# CLK_INPUT.net
KiCad netlist of a schematic drawn in Altium Designer
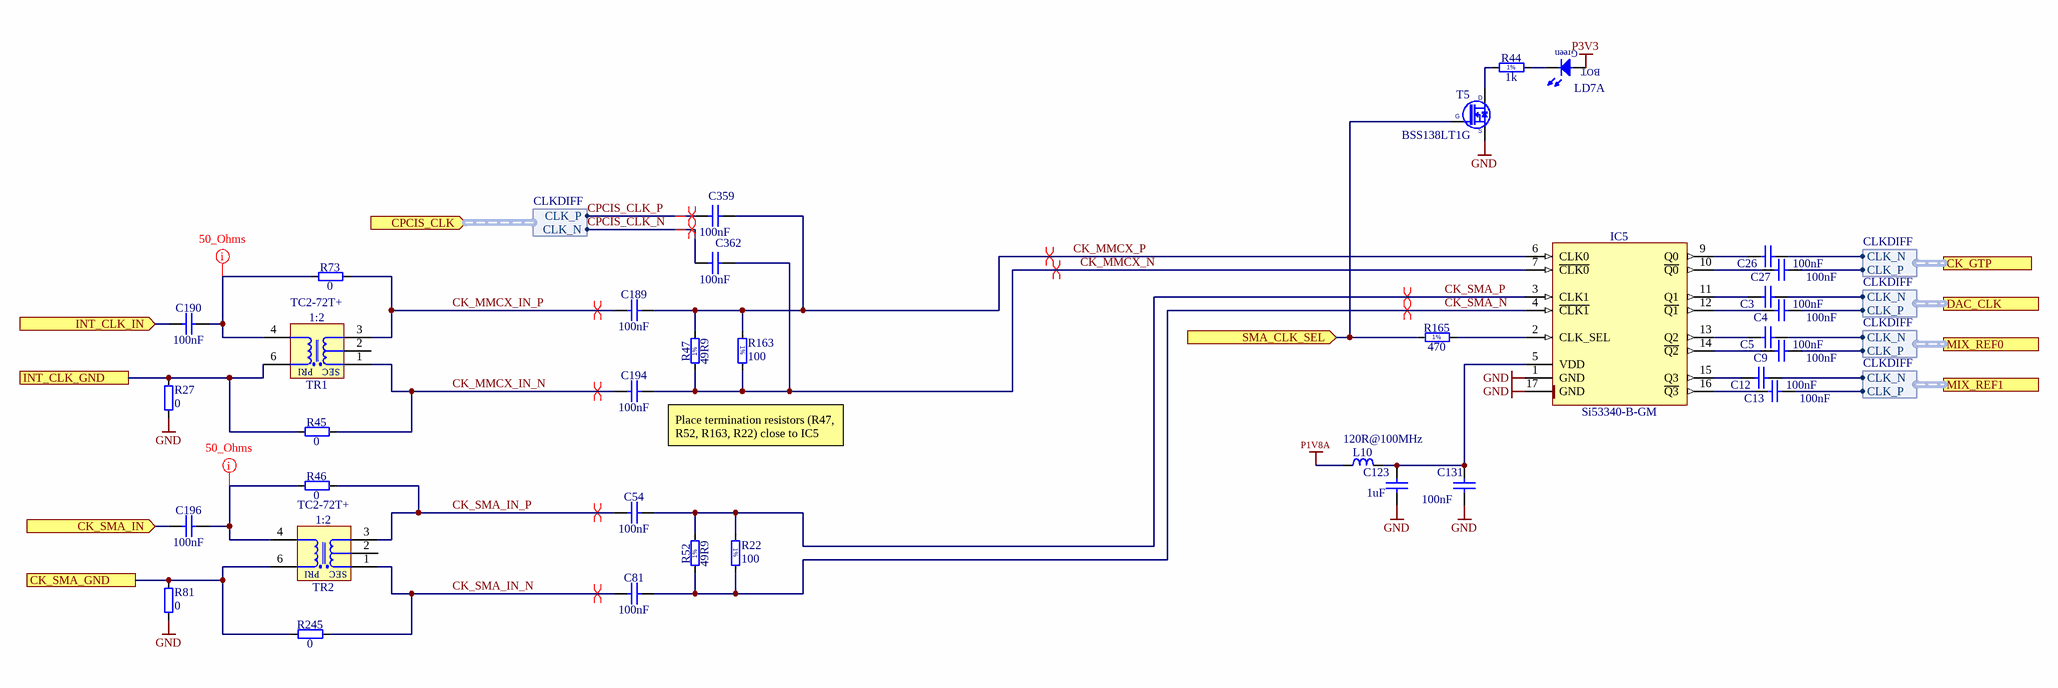
[diagram p0: CLK_INPUT.SchDoc]

(export (version "E")
  (design (tool "Eeschema 10.0.6"))
  (components
    (comp (ref "C3")
      (value "100nF")
      (footprint "CAPC1005X55N")
      (description "Non-polarised capacitor")
      (fields
        (field (name "PART NUMBER") "CC0402_100NF_16V_10%_X5R")
        (field (name "VOLTAGE") "16V")
        (field (name "AUTHOR") "CERN DEM JLC")
      )
      (libsource (lib "Capacitors") (part "Capacitor - non polarized"))
    )
    (comp (ref "C4")
      (value "100nF")
      (footprint "CAPC1005X55N")
      (description "Non-polarised capacitor")
      (fields
        (field (name "PART NUMBER") "CC0402_100NF_16V_10%_X5R")
        (field (name "VOLTAGE") "16V")
        (field (name "AUTHOR") "CERN DEM JLC")
      )
      (libsource (lib "Capacitors") (part "Capacitor - non polarized"))
    )
    (comp (ref "C5")
      (value "100nF")
      (footprint "CAPC1005X55N")
      (description "Non-polarised capacitor")
      (fields
        (field (name "PART NUMBER") "CC0402_100NF_16V_10%_X5R")
        (field (name "VOLTAGE") "16V")
        (field (name "AUTHOR") "CERN DEM JLC")
      )
      (libsource (lib "Capacitors") (part "Capacitor - non polarized"))
    )
    (comp (ref "C9")
      (value "100nF")
      (footprint "CAPC1005X55N")
      (description "Non-polarised capacitor")
      (fields
        (field (name "PART NUMBER") "CC0402_100NF_16V_10%_X5R")
        (field (name "VOLTAGE") "16V")
        (field (name "AUTHOR") "CERN DEM JLC")
      )
      (libsource (lib "Capacitors") (part "Capacitor - non polarized"))
    )
    (comp (ref "C12")
      (value "100nF")
      (footprint "CAPC1005X55N")
      (description "Non-polarised capacitor")
      (fields
        (field (name "PART NUMBER") "CC0402_100NF_16V_10%_X5R")
        (field (name "VOLTAGE") "16V")
        (field (name "AUTHOR") "CERN DEM JLC")
      )
      (libsource (lib "Capacitors") (part "Capacitor - non polarized"))
    )
    (comp (ref "C13")
      (value "100nF")
      (footprint "CAPC1005X55N")
      (description "Non-polarised capacitor")
      (fields
        (field (name "PART NUMBER") "CC0402_100NF_16V_10%_X5R")
        (field (name "VOLTAGE") "16V")
        (field (name "AUTHOR") "CERN DEM JLC")
      )
      (libsource (lib "Capacitors") (part "Capacitor - non polarized"))
    )
    (comp (ref "C26")
      (value "100nF")
      (footprint "CAPC1005X55N")
      (description "Non-polarised capacitor")
      (fields
        (field (name "PART NUMBER") "CC0402_100NF_16V_10%_X5R")
        (field (name "VOLTAGE") "16V")
        (field (name "AUTHOR") "CERN DEM JLC")
      )
      (libsource (lib "Capacitors") (part "Capacitor - non polarized"))
    )
    (comp (ref "C27")
      (value "100nF")
      (footprint "CAPC1005X55N")
      (description "Non-polarised capacitor")
      (fields
        (field (name "PART NUMBER") "CC0402_100NF_16V_10%_X5R")
        (field (name "VOLTAGE") "16V")
        (field (name "AUTHOR") "CERN DEM JLC")
      )
      (libsource (lib "Capacitors") (part "Capacitor - non polarized"))
    )
    (comp (ref "C54")
      (value "100nF")
      (footprint "CAPC1005X55N")
      (description "Non-polarised capacitor")
      (fields
        (field (name "PART NUMBER") "CC0402_100NF_16V_10%_X5R")
        (field (name "VOLTAGE") "16V")
        (field (name "AUTHOR") "CERN DEM JLC")
      )
      (libsource (lib "Capacitors") (part "Capacitor - non polarized"))
    )
    (comp (ref "C81")
      (value "100nF")
      (footprint "CAPC1005X55N")
      (description "Non-polarised capacitor")
      (fields
        (field (name "PART NUMBER") "CC0402_100NF_16V_10%_X5R")
        (field (name "VOLTAGE") "16V")
        (field (name "AUTHOR") "CERN DEM JLC")
      )
      (libsource (lib "Capacitors") (part "Capacitor - non polarized"))
    )
    (comp (ref "C123")
      (value "1uF")
      (footprint "CAPC1005X55N")
      (description "Non-polarised capacitor")
      (fields
        (field (name "PART NUMBER") "CC0402_1UF_16V_10%_X5R")
        (field (name "VOLTAGE") "16V")
        (field (name "AUTHOR") "CERN DEM JLC")
      )
      (libsource (lib "Capacitors") (part "Capacitor - non polarized"))
    )
    (comp (ref "C131")
      (value "100nF")
      (footprint "CAPC1005X55N")
      (description "Non-polarised capacitor")
      (fields
        (field (name "PART NUMBER") "CC0402_100NF_16V_10%_X5R")
        (field (name "VOLTAGE") "16V")
        (field (name "AUTHOR") "CERN DEM JLC")
      )
      (libsource (lib "Capacitors") (part "Capacitor - non polarized"))
    )
    (comp (ref "C189")
      (value "100nF")
      (footprint "CAPC1005X55N")
      (description "Non-polarised capacitor")
      (fields
        (field (name "PART NUMBER") "CC0402_100NF_16V_10%_X5R")
        (field (name "VOLTAGE") "16V")
        (field (name "AUTHOR") "CERN DEM JLC")
      )
      (libsource (lib "Capacitors") (part "Capacitor - non polarized"))
    )
    (comp (ref "C190")
      (value "100nF")
      (footprint "CAPC1005X55N")
      (description "Non-polarised capacitor")
      (fields
        (field (name "PART NUMBER") "CC0402_100NF_16V_10%_X5R")
        (field (name "VOLTAGE") "16V")
        (field (name "AUTHOR") "CERN DEM JLC")
      )
      (libsource (lib "Capacitors") (part "Capacitor - non polarized"))
    )
    (comp (ref "C194")
      (value "100nF")
      (footprint "CAPC1005X55N")
      (description "Non-polarised capacitor")
      (fields
        (field (name "PART NUMBER") "CC0402_100NF_16V_10%_X5R")
        (field (name "VOLTAGE") "16V")
        (field (name "AUTHOR") "CERN DEM JLC")
      )
      (libsource (lib "Capacitors") (part "Capacitor - non polarized"))
    )
    (comp (ref "C196")
      (value "100nF")
      (footprint "CAPC1005X55N")
      (description "Non-polarised capacitor")
      (fields
        (field (name "PART NUMBER") "CC0402_100NF_16V_10%_X5R")
        (field (name "VOLTAGE") "16V")
        (field (name "AUTHOR") "CERN DEM JLC")
      )
      (libsource (lib "Capacitors") (part "Capacitor - non polarized"))
    )
    (comp (ref "C359")
      (value "100nF")
      (footprint "CAPC1005X55N")
      (description "Non-polarised capacitor")
      (fields
        (field (name "PART NUMBER") "CC0402_100NF_16V_10%_X5R")
        (field (name "VOLTAGE") "16V")
        (field (name "AUTHOR") "CERN DEM JLC")
      )
      (libsource (lib "Capacitors") (part "Capacitor - non polarized"))
    )
    (comp (ref "C362")
      (value "100nF")
      (footprint "CAPC1005X55N")
      (description "Non-polarised capacitor")
      (fields
        (field (name "PART NUMBER") "CC0402_100NF_16V_10%_X5R")
        (field (name "VOLTAGE") "16V")
        (field (name "AUTHOR") "CERN DEM JLC")
      )
      (libsource (lib "Capacitors") (part "Capacitor - non polarized"))
    )
    (comp (ref "IC5")
      (value "Si53340-B-GM")
      (footprint "QFN50P300X300X90-17N-S175")
      (description "Low-Jitter LVDS Fanout Clock Buffers, 10-Output,  Any-Input, Any-Frequency up to 1250MHz")
      (fields (field (name "MANUFACTURER") "SILICON LABS") (field (name "AUTHOR") "CERN DEM MR"))
      (libsource (lib "ICs And Semiconductors") (part "Si53340"))
    )
    (comp (ref "L10")
      (value "120R@100MHz")
      (footprint "INDC1608X95N")
      (description "Inductor")
      (fields
        (field (name "PART NUMBER") "IND0603_MURATA_BLM18PG121SN1D")
        (field (name "POWER") "2A")
        (field (name "AUTHOR") "CERN DEM BC")
      )
      (libsource (lib "Inductors & Transformers") (part "Inductor"))
    )
    (comp (ref "LD7")
      (value "Red/Green")
      (footprint "LED_DIALIGHT_571-0112F")
      (description "2x LED  Botom Green, Top Red")
      (fields
        (field (name "PART NUMBER") "LED_DIALIGHT_571-0112F")
        (field (name "MANUFACTURER") "DIALIGHT")
        (field (name "AUTHOR") "CERN DEM JLC")
      )
      (libsource (lib "ICs And Semiconductors") (part "LED x2 G-1C2A-BOT_R-3C4A-TOP"))
    )
    (comp (ref "R22")
      (value "100")
      (footprint "RESC1005X40N")
      (description "Resistor - 1%")
      (fields
        (field (name "PART NUMBER") "R0402_100R_1%_0.0625W_100PPM")
        (field (name "POWER") "0.0625W")
        (field (name "AUTHOR") "CERN DEM JLC")
      )
      (libsource (lib "Resistors") (part "Resistor - 1%"))
    )
    (comp (ref "R27")
      (value "0")
      (footprint "RESC1005X40N")
      (description "Resistor")
      (fields
        (field (name "PART NUMBER") "R0402_0R_JUMPER")
        (field (name "MANUFACTURER") "GENERIC")
        (field (name "AUTHOR") "CERN DEM JLC")
      )
      (libsource (lib "Resistors") (part "Resistor"))
    )
    (comp (ref "R44")
      (value "1k")
      (footprint "RESC1005X40N")
      (description "Resistor - 1%")
      (fields
        (field (name "PART NUMBER") "R0402_1K_1%_0.0625W_100PPM")
        (field (name "POWER") "0.0625W")
        (field (name "AUTHOR") "CERN DEM JLC")
      )
      (libsource (lib "Resistors") (part "Resistor - 1%"))
    )
    (comp (ref "R45")
      (value "0")
      (footprint "RESC1005X40N")
      (description "Resistor")
      (fields
        (field (name "PART NUMBER") "R0402_0R_JUMPER")
        (field (name "MANUFACTURER") "GENERIC")
        (field (name "AUTHOR") "CERN DEM JLC")
      )
      (libsource (lib "Resistors") (part "Resistor"))
    )
    (comp (ref "R46")
      (value "0")
      (footprint "RESC1005X40N")
      (description "Resistor")
      (fields
        (field (name "PART NUMBER") "R0402_0R_JUMPER")
        (field (name "MANUFACTURER") "GENERIC")
        (field (name "AUTHOR") "CERN DEM JLC")
      )
      (libsource (lib "Resistors") (part "Resistor"))
    )
    (comp (ref "R47")
      (value "49R9")
      (footprint "RESC1005X40N")
      (description "Resistor - 1%")
      (fields
        (field (name "PART NUMBER") "R0402_49R9_1%_0.0625W_100PPM")
        (field (name "POWER") "0.0625W")
        (field (name "AUTHOR") "CERN DEM JLC")
      )
      (libsource (lib "Resistors") (part "Resistor - 1%"))
    )
    (comp (ref "R52")
      (value "49R9")
      (footprint "RESC1005X40N")
      (description "Resistor - 1%")
      (fields
        (field (name "PART NUMBER") "R0402_49R9_1%_0.0625W_100PPM")
        (field (name "POWER") "0.0625W")
        (field (name "AUTHOR") "CERN DEM JLC")
      )
      (libsource (lib "Resistors") (part "Resistor - 1%"))
    )
    (comp (ref "R73")
      (value "0")
      (footprint "RESC1005X40N")
      (description "Resistor")
      (fields
        (field (name "PART NUMBER") "R0402_0R_JUMPER")
        (field (name "MANUFACTURER") "GENERIC")
        (field (name "AUTHOR") "CERN DEM JLC")
      )
      (libsource (lib "Resistors") (part "Resistor"))
    )
    (comp (ref "R81")
      (value "0")
      (footprint "RESC1005X40N")
      (description "Resistor")
      (fields
        (field (name "PART NUMBER") "R0402_0R_JUMPER")
        (field (name "MANUFACTURER") "GENERIC")
        (field (name "AUTHOR") "CERN DEM JLC")
      )
      (libsource (lib "Resistors") (part "Resistor"))
    )
    (comp (ref "R163")
      (value "100")
      (footprint "RESC1005X40N")
      (description "Resistor - 1%")
      (fields
        (field (name "PART NUMBER") "R0402_100R_1%_0.0625W_100PPM")
        (field (name "POWER") "0.0625W")
        (field (name "AUTHOR") "CERN DEM JLC")
      )
      (libsource (lib "Resistors") (part "Resistor - 1%"))
    )
    (comp (ref "R165")
      (value "470")
      (footprint "RESC1005X40N")
      (description "Resistor - 1%")
      (fields
        (field (name "PART NUMBER") "R0402_470R_1%_0.0625W_100PPM")
        (field (name "POWER") "0.0625W")
        (field (name "AUTHOR") "CERN DEM JLC")
      )
      (libsource (lib "Resistors") (part "Resistor - 1%"))
    )
    (comp (ref "R245")
      (value "0")
      (footprint "RESC1005X40N")
      (description "Resistor")
      (fields
        (field (name "PART NUMBER") "R0402_0R_JUMPER")
        (field (name "MANUFACTURER") "GENERIC")
        (field (name "AUTHOR") "CERN DEM JLC")
      )
      (libsource (lib "Resistors") (part "Resistor"))
    )
    (comp (ref "T5")
      (value "BSS138LT1G")
      (footprint "SOT95P240X110-3N")
      (description "N-CHANNEL MOSFET WITH DIODE")
      (fields (field (name "MANUFACTURER") "ON SEMICONDUCTOR") (field (name "AUTHOR") "CERN DEM JLC"))
      (libsource (lib "ICs And Semiconductors") (part "N-MOSFET-D 1G 2S 3D"))
    )
    (comp (ref "TR1")
      (value "1:2")
      (footprint "XFMR_MINI-CIRCUITS_AT1521")
      (description "50 Ohms 10 to 700 MHzz RF Transformer")
      (fields
        (field (name "MANUFACTURER") "MINI-CIRCUITS")
        (field (name "MANUFACTURER PART NUMBER") "TC2-72T+")
        (field (name "PART NUMBER") "XFMR_MINI-CIRCUITS_TC2-72T+")
        (field (name "AUTHOR") "GK")
      )
      (libsource (lib "Inductors_Transformers") (part "XFMR_MINI-CIRCUITS_TC2-72T+"))
    )
    (comp (ref "TR2")
      (value "1:2")
      (footprint "XFMR_MINI-CIRCUITS_AT1521")
      (description "50 Ohms 10 to 700 MHzz RF Transformer")
      (fields
        (field (name "MANUFACTURER") "MINI-CIRCUITS")
        (field (name "MANUFACTURER PART NUMBER") "TC2-72T+")
        (field (name "PART NUMBER") "XFMR_MINI-CIRCUITS_TC2-72T+")
        (field (name "AUTHOR") "GK")
      )
      (libsource (lib "Inductors_Transformers") (part "XFMR_MINI-CIRCUITS_TC2-72T+"))
    )
  )
  (nets
    (net (code "2") (name "/CK_MMCX_IN_N") (class "Default")
      (node (ref "C194") (pin "1") (pinfunction "1_1") (pintype "passive"))
      (node (ref "R45") (pin "2") (pinfunction "2_2") (pintype "passive"))
      (node (ref "TR1") (pin "1") (pinfunction "SDOT_1") (pintype "passive"))
    )
    (net (code "3") (name "/CK_MMCX_IN_P") (class "Default")
      (node (ref "C189") (pin "1") (pinfunction "1_1") (pintype "passive"))
      (node (ref "R73") (pin "2") (pinfunction "2_2") (pintype "passive"))
      (node (ref "TR1") (pin "3") (pinfunction "S_3") (pintype "passive"))
    )
    (net (code "4") (name "/CK_MMCX_N") (class "Default")
      (node (ref "C194") (pin "2") (pinfunction "2_2") (pintype "passive"))
      (node (ref "C362") (pin "2") (pinfunction "2_2") (pintype "passive"))
      (node (ref "IC5") (pin "7") (pinfunction "~{CLK0}_7") (pintype "input"))
      (node (ref "R163") (pin "2") (pinfunction "2_2") (pintype "passive"))
      (node (ref "R47") (pin "1") (pinfunction "1_1") (pintype "passive"))
    )
    (net (code "5") (name "/CK_MMCX_P") (class "Default")
      (node (ref "C189") (pin "2") (pinfunction "2_2") (pintype "passive"))
      (node (ref "C359") (pin "2") (pinfunction "2_2") (pintype "passive"))
      (node (ref "IC5") (pin "6") (pinfunction "CLK0_6") (pintype "input"))
      (node (ref "R163") (pin "1") (pinfunction "1_1") (pintype "passive"))
      (node (ref "R47") (pin "2") (pinfunction "2_2") (pintype "passive"))
    )
    (net (code "6") (name "/CK_SMA_GND") (class "Default")
      (node (ref "R245") (pin "1") (pinfunction "1_1") (pintype "passive"))
      (node (ref "R81") (pin "2") (pinfunction "2_2") (pintype "passive"))
      (node (ref "TR2") (pin "6") (pinfunction "PDOT_6") (pintype "passive"))
    )
    (net (code "7") (name "/CK_SMA_IN") (class "Default")
      (node (ref "C196") (pin "1") (pinfunction "1_1") (pintype "passive"))
    )
    (net (code "8") (name "/CK_SMA_IN_N") (class "Default")
      (node (ref "C81") (pin "1") (pinfunction "1_1") (pintype "passive"))
      (node (ref "R245") (pin "2") (pinfunction "2_2") (pintype "passive"))
      (node (ref "TR2") (pin "1") (pinfunction "SDOT_1") (pintype "passive"))
    )
    (net (code "9") (name "/CK_SMA_IN_P") (class "Default")
      (node (ref "C54") (pin "1") (pinfunction "1_1") (pintype "passive"))
      (node (ref "R46") (pin "2") (pinfunction "2_2") (pintype "passive"))
      (node (ref "TR2") (pin "3") (pinfunction "S_3") (pintype "passive"))
    )
    (net (code "10") (name "/CK_SMA_N") (class "Default")
      (node (ref "C81") (pin "2") (pinfunction "2_2") (pintype "passive"))
      (node (ref "IC5") (pin "4") (pinfunction "~{CLK1}_4") (pintype "input"))
      (node (ref "R22") (pin "2") (pinfunction "2_2") (pintype "passive"))
      (node (ref "R52") (pin "1") (pinfunction "1_1") (pintype "passive"))
    )
    (net (code "11") (name "/CK_SMA_P") (class "Default")
      (node (ref "C54") (pin "2") (pinfunction "2_2") (pintype "passive"))
      (node (ref "IC5") (pin "3") (pinfunction "CLK1_3") (pintype "input"))
      (node (ref "R22") (pin "1") (pinfunction "1_1") (pintype "passive"))
      (node (ref "R52") (pin "2") (pinfunction "2_2") (pintype "passive"))
    )
    (net (code "12") (name "/CPCIS_CLK_N") (class "Default")
      (node (ref "C362") (pin "1") (pinfunction "1_1") (pintype "passive"))
    )
    (net (code "13") (name "/CPCIS_CLK_P") (class "Default")
      (node (ref "C359") (pin "1") (pinfunction "1_1") (pintype "passive"))
    )
    (net (code "14") (name "/INT_CLK_GND") (class "Default")
      (node (ref "R27") (pin "2") (pinfunction "2_2") (pintype "passive"))
      (node (ref "R45") (pin "1") (pinfunction "1_1") (pintype "passive"))
      (node (ref "TR1") (pin "6") (pinfunction "PDOT_6") (pintype "passive"))
    )
    (net (code "15") (name "/INT_CLK_IN") (class "Default")
      (node (ref "C190") (pin "1") (pinfunction "1_1") (pintype "passive"))
    )
    (net (code "16") (name "/SMA_CLK_SEL") (class "Default")
      (node (ref "R165") (pin "1") (pinfunction "1_1") (pintype "passive"))
      (node (ref "T5") (pin "1") (pinfunction "G_1") (pintype "passive"))
    )
    (net (code "18") (name "GND") (class "Default")
      (node (ref "C123") (pin "1") (pinfunction "1_1") (pintype "passive"))
      (node (ref "C131") (pin "1") (pinfunction "1_1") (pintype "passive"))
      (node (ref "IC5") (pin "1") (pinfunction "GND_1") (pintype "power_in"))
      (node (ref "IC5") (pin "17") (pinfunction "GND_17") (pintype "power_in"))
      (node (ref "R27") (pin "1") (pinfunction "1_1") (pintype "passive"))
      (node (ref "R81") (pin "1") (pinfunction "1_1") (pintype "passive"))
      (node (ref "T5") (pin "2") (pinfunction "S_2") (pintype "passive"))
    )
    (net (code "19") (name "Net-(IC5-CLK_SEL)") (class "Default")
      (node (ref "IC5") (pin "2") (pinfunction "CLK_SEL_2") (pintype "input"))
      (node (ref "R165") (pin "2") (pinfunction "2_2") (pintype "passive"))
    )
    (net (code "20") (name "Net-(IC5-Q0)") (class "Default")
      (node (ref "C26") (pin "1") (pinfunction "1_1") (pintype "passive"))
      (node (ref "IC5") (pin "9") (pinfunction "Q0_9") (pintype "output"))
    )
    (net (code "21") (name "Net-(IC5-Q1)") (class "Default")
      (node (ref "C3") (pin "1") (pinfunction "1_1") (pintype "passive"))
      (node (ref "IC5") (pin "11") (pinfunction "Q1_11") (pintype "output"))
    )
    (net (code "22") (name "Net-(IC5-Q2)") (class "Default")
      (node (ref "C5") (pin "1") (pinfunction "1_1") (pintype "passive"))
      (node (ref "IC5") (pin "13") (pinfunction "Q2_13") (pintype "output"))
    )
    (net (code "23") (name "Net-(IC5-Q3)") (class "Default")
      (node (ref "C12") (pin "1") (pinfunction "1_1") (pintype "passive"))
      (node (ref "IC5") (pin "15") (pinfunction "Q3_15") (pintype "output"))
    )
    (net (code "24") (name "Net-(IC5-VDD)") (class "Default")
      (node (ref "C123") (pin "2") (pinfunction "2_2") (pintype "passive"))
      (node (ref "C131") (pin "2") (pinfunction "2_2") (pintype "passive"))
      (node (ref "IC5") (pin "5") (pinfunction "VDD_5") (pintype "power_in"))
      (node (ref "L10") (pin "1") (pinfunction "1_1") (pintype "passive"))
    )
    (net (code "25") (name "Net-(IC5-~{Q0})") (class "Default")
      (node (ref "C27") (pin "1") (pinfunction "1_1") (pintype "passive"))
      (node (ref "IC5") (pin "10") (pinfunction "~{Q0}_10") (pintype "output"))
    )
    (net (code "26") (name "Net-(IC5-~{Q1})") (class "Default")
      (node (ref "C4") (pin "1") (pinfunction "1_1") (pintype "passive"))
      (node (ref "IC5") (pin "12") (pinfunction "~{Q1}_12") (pintype "output"))
    )
    (net (code "27") (name "Net-(IC5-~{Q2})") (class "Default")
      (node (ref "C9") (pin "1") (pinfunction "1_1") (pintype "passive"))
      (node (ref "IC5") (pin "14") (pinfunction "~{Q2}_14") (pintype "output"))
    )
    (net (code "28") (name "Net-(IC5-~{Q3})") (class "Default")
      (node (ref "C13") (pin "1") (pinfunction "1_1") (pintype "passive"))
      (node (ref "IC5") (pin "16") (pinfunction "~{Q3}_16") (pintype "output"))
    )
    (net (code "29") (name "Net-(LD7A-C)") (class "Default")
      (node (ref "LD7") (pin "1") (pinfunction "C_1") (pintype "passive"))
      (node (ref "R44") (pin "2") (pinfunction "2_2") (pintype "passive"))
    )
    (net (code "30") (name "Net-(T5-D)") (class "Default")
      (node (ref "R44") (pin "1") (pinfunction "1_1") (pintype "passive"))
      (node (ref "T5") (pin "3") (pinfunction "D_3") (pintype "passive"))
    )
    (net (code "31") (name "Net-(TR1-P)") (class "Default")
      (node (ref "C190") (pin "2") (pinfunction "2_2") (pintype "passive"))
      (node (ref "R73") (pin "1") (pinfunction "1_1") (pintype "passive"))
      (node (ref "TR1") (pin "4") (pinfunction "P_4") (pintype "passive"))
    )
    (net (code "32") (name "Net-(TR2-P)") (class "Default")
      (node (ref "C196") (pin "2") (pinfunction "2_2") (pintype "passive"))
      (node (ref "R46") (pin "1") (pinfunction "1_1") (pintype "passive"))
      (node (ref "TR2") (pin "4") (pinfunction "P_4") (pintype "passive"))
    )
    (net (code "33") (name "P1V8A") (class "Default")
      (node (ref "L10") (pin "2") (pinfunction "2_2") (pintype "passive"))
    )
    (net (code "34") (name "P3V3") (class "Default")
      (node (ref "LD7") (pin "2") (pinfunction "A_2") (pintype "passive"))
    )
    (net (code "35") (name "unconnected-(C3-Pad2)") (class "Default")
      (node (ref "C3") (pin "2") (pinfunction "2_2") (pintype "passive"))
    )
    (net (code "36") (name "unconnected-(C4-Pad2)") (class "Default")
      (node (ref "C4") (pin "2") (pinfunction "2_2") (pintype "passive"))
    )
    (net (code "37") (name "unconnected-(C5-Pad2)") (class "Default")
      (node (ref "C5") (pin "2") (pinfunction "2_2") (pintype "passive"))
    )
    (net (code "38") (name "unconnected-(C9-Pad2)") (class "Default")
      (node (ref "C9") (pin "2") (pinfunction "2_2") (pintype "passive"))
    )
    (net (code "39") (name "unconnected-(C12-Pad2)") (class "Default")
      (node (ref "C12") (pin "2") (pinfunction "2_2") (pintype "passive"))
    )
    (net (code "40") (name "unconnected-(C13-Pad2)") (class "Default")
      (node (ref "C13") (pin "2") (pinfunction "2_2") (pintype "passive"))
    )
    (net (code "41") (name "unconnected-(C26-Pad2)") (class "Default")
      (node (ref "C26") (pin "2") (pinfunction "2_2") (pintype "passive"))
    )
    (net (code "42") (name "unconnected-(C27-Pad2)") (class "Default")
      (node (ref "C27") (pin "2") (pinfunction "2_2") (pintype "passive"))
    )
    (net (code "43") (name "unconnected-(TR1-NC-Pad2)") (class "Default")
      (node (ref "TR1") (pin "2") (pinfunction "NC_2") (pintype "passive"))
    )
    (net (code "44") (name "unconnected-(TR2-NC-Pad2)") (class "Default")
      (node (ref "TR2") (pin "2") (pinfunction "NC_2") (pintype "passive"))
    )
  )
)
